# SCH_touchsensor_pressure_2024-07-11.net
KiCad netlist of a schematic drawn in EasyEDA
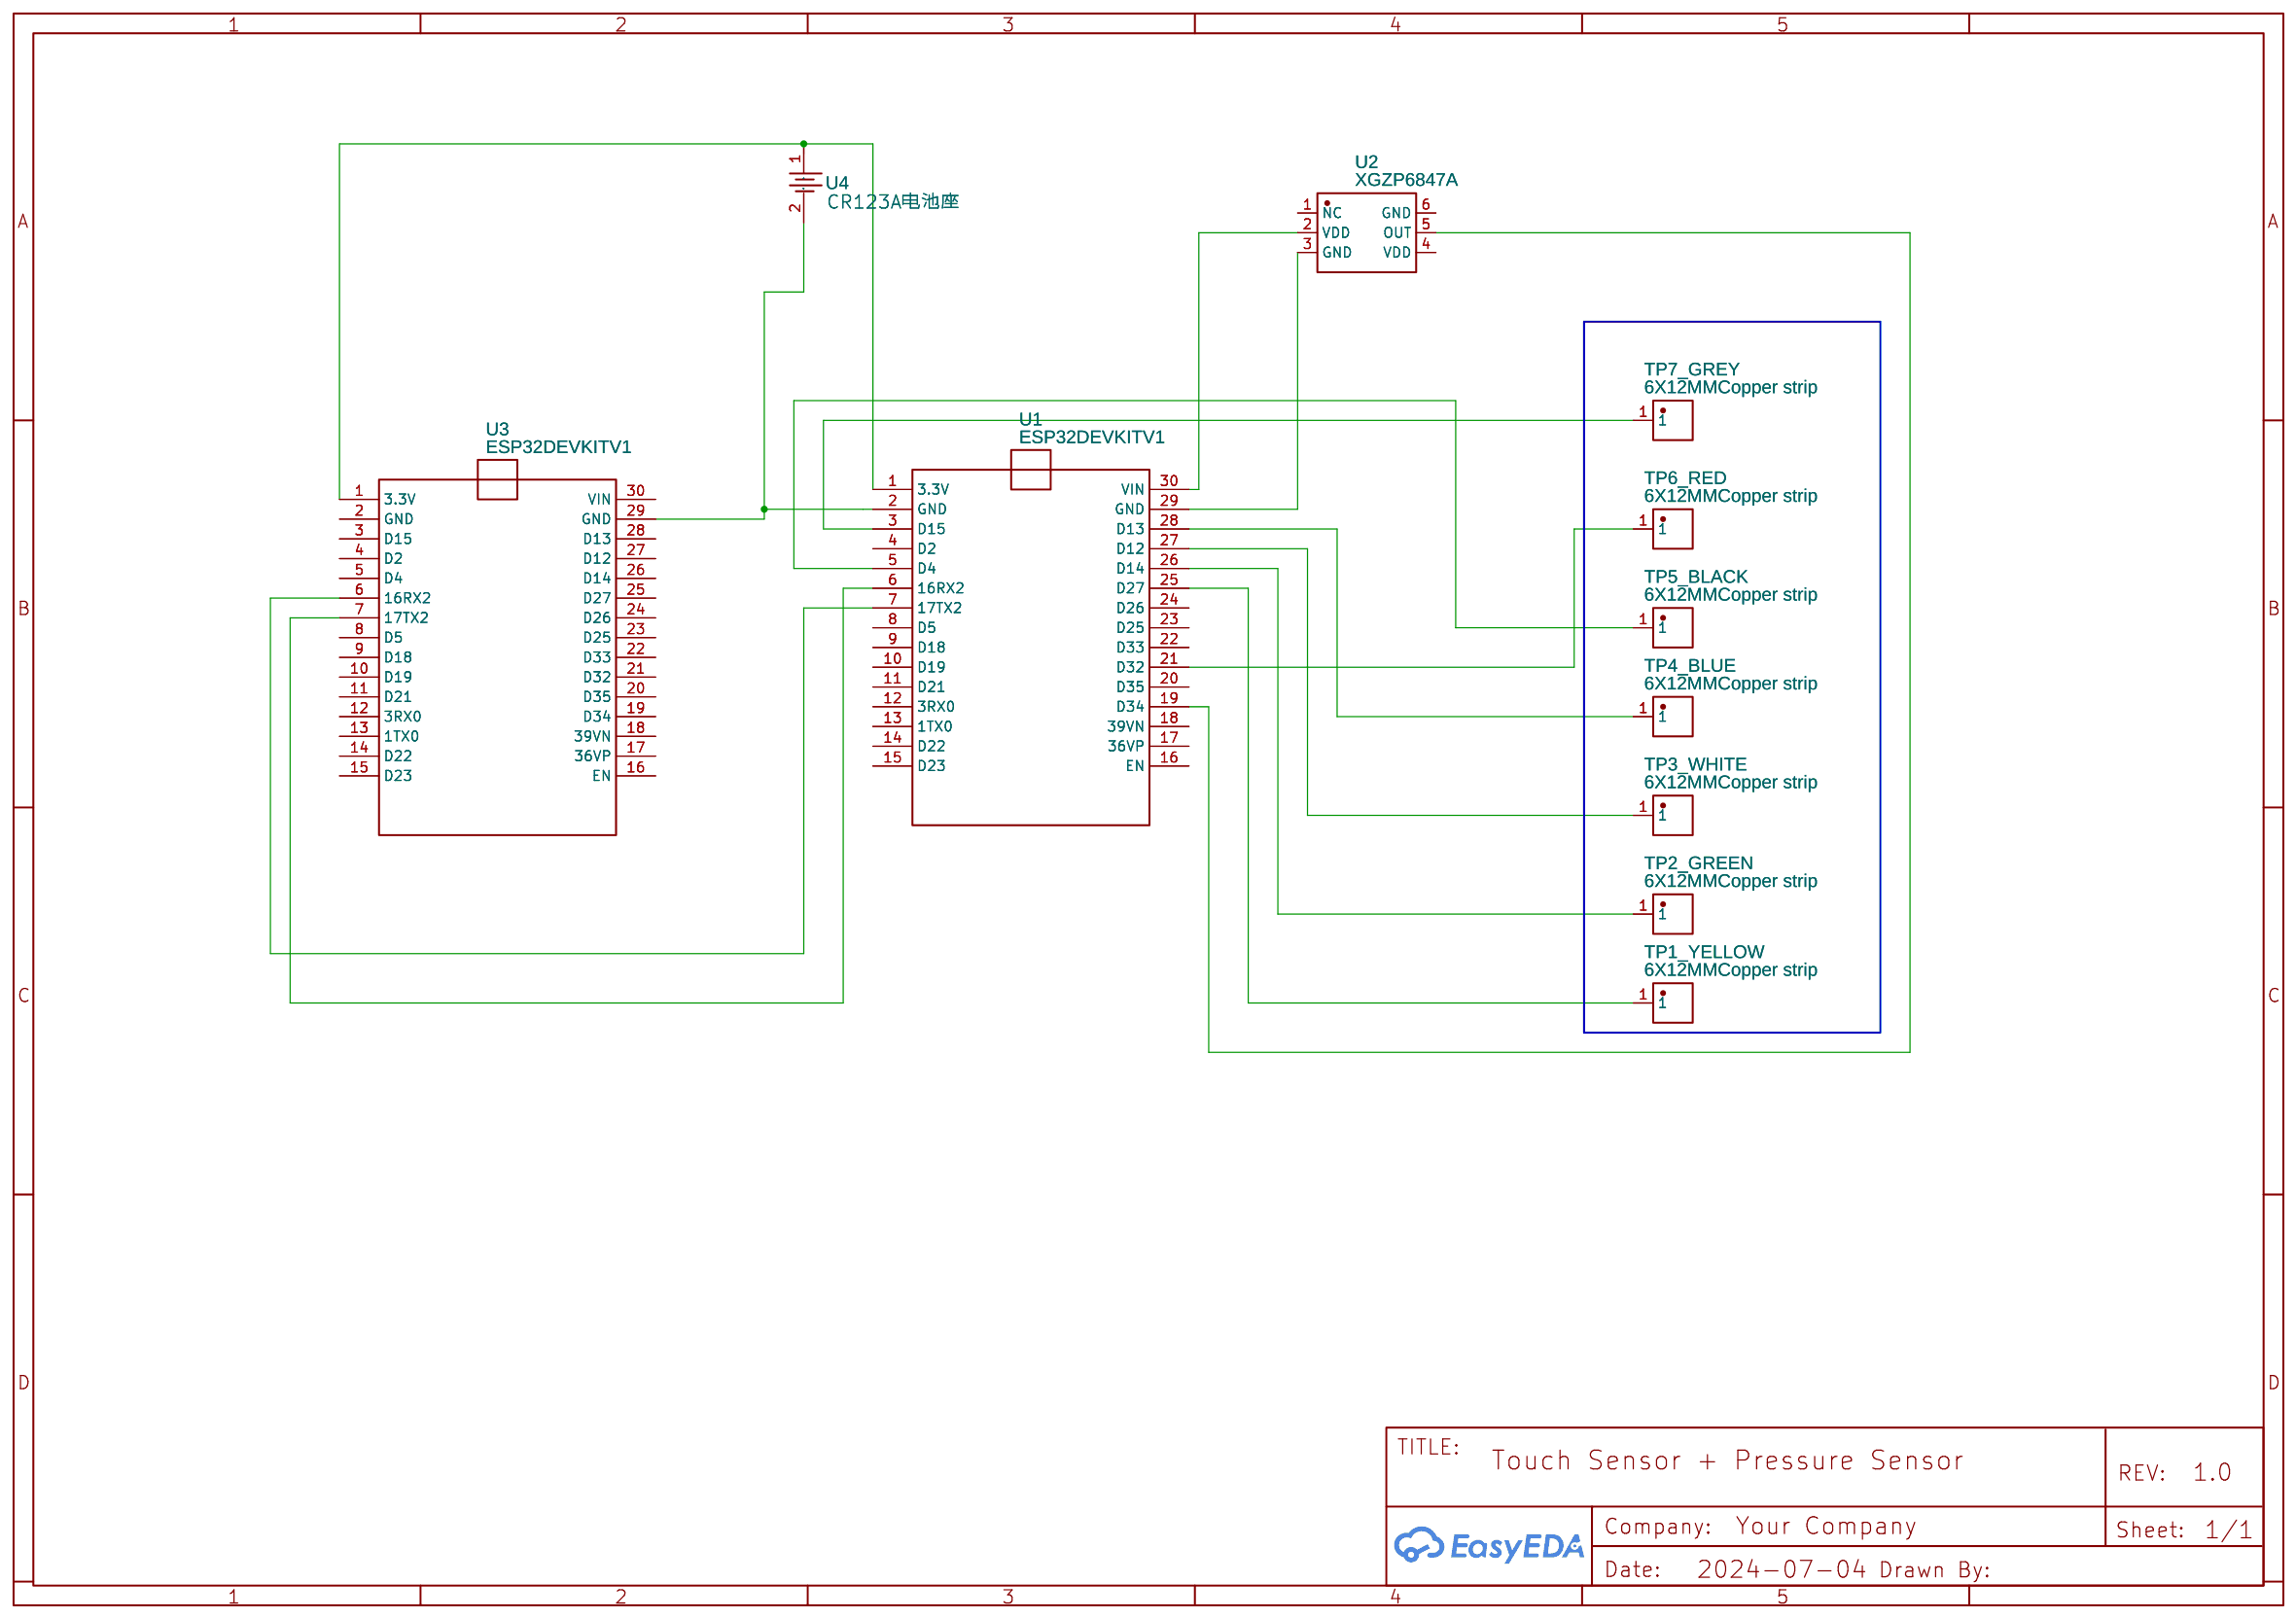
[diagram p0: schematic sheet]

(export (version "E")
  (design (tool "Eeschema 10.0.6"))
  (components
    (comp (ref "TP1_YELLOW")
      (value "6X12MMCopper strip")
      (fields (field (name "Manufacturer Part") "6X12mm铜片"))
      (libsource (lib "") (part "6X12MMCopper strip_3"))
    )
    (comp (ref "TP2_GREEN")
      (value "6X12MMCopper strip")
      (fields (field (name "Manufacturer Part") "6X12mm铜片"))
      (libsource (lib "") (part "6X12MMCopper strip"))
    )
    (comp (ref "TP3_WHITE")
      (value "6X12MMCopper strip")
      (fields (field (name "Manufacturer Part") "6X12mm铜片"))
      (libsource (lib "") (part "6X12MMCopper strip_2"))
    )
    (comp (ref "TP4_BLUE")
      (value "6X12MMCopper strip")
      (fields (field (name "Manufacturer Part") "6X12mm铜片"))
      (libsource (lib "") (part "6X12MMCopper strip_5"))
    )
    (comp (ref "TP5_BLACK")
      (value "6X12MMCopper strip")
      (fields (field (name "Manufacturer Part") "6X12mm铜片"))
      (libsource (lib "") (part "6X12MMCopper strip_1"))
    )
    (comp (ref "TP6_RED")
      (value "6X12MMCopper strip")
      (fields (field (name "Manufacturer Part") "6X12mm铜片"))
      (libsource (lib "") (part "6X12MMCopper strip_4"))
    )
    (comp (ref "TP7_GREY")
      (value "6X12MMCopper strip")
      (fields (field (name "Manufacturer Part") "6X12mm铜片"))
      (libsource (lib "") (part "6X12MMCopper strip_6"))
    )
    (comp (ref "U1") (value "ESP32DEVKITV1") (libsource (lib "") (part "ESP32DEVKITV1")))
    (comp (ref "U2") (value "XGZP6847A") (libsource (lib "") (part "XGZP6847A")))
    (comp (ref "U3") (value "ESP32DEVKITV1") (libsource (lib "") (part "ESP32DEVKITV1")))
    (comp (ref "U4") (value "CR123A电池座") (libsource (lib "") (part "CR123A电池座")))
  )
  (nets
    (net (code "1") (name "Net-(U1-3.3V)") (class "Default")
      (node (ref "U1") (pin "1") (pinfunction "3.3V_1") (pintype "unspecified"))
      (node (ref "U3") (pin "1") (pinfunction "3.3V_1") (pintype "unspecified"))
      (node (ref "U4") (pin "1") (pinfunction "1_1") (pintype "input"))
    )
    (net (code "2") (name "Net-(U1-16RX2)") (class "Default")
      (node (ref "U1") (pin "6") (pinfunction "16RX2_6") (pintype "unspecified"))
      (node (ref "U3") (pin "7") (pinfunction "17TX2_7") (pintype "unspecified"))
    )
    (net (code "3") (name "Net-(U1-17TX2)") (class "Default")
      (node (ref "U1") (pin "7") (pinfunction "17TX2_7") (pintype "unspecified"))
      (node (ref "U3") (pin "6") (pinfunction "16RX2_6") (pintype "unspecified"))
    )
    (net (code "4") (name "Net-(U1-D4)") (class "Default")
      (node (ref "TP5_BLACK") (pin "1") (pinfunction "1_1") (pintype "unspecified"))
      (node (ref "U1") (pin "5") (pinfunction "D4_5") (pintype "unspecified"))
    )
    (net (code "5") (name "Net-(U1-D12)") (class "Default")
      (node (ref "TP3_WHITE") (pin "1") (pinfunction "1_1") (pintype "unspecified"))
      (node (ref "U1") (pin "27") (pinfunction "D12_27") (pintype "unspecified"))
    )
    (net (code "6") (name "Net-(U1-D13)") (class "Default")
      (node (ref "TP4_BLUE") (pin "1") (pinfunction "1_1") (pintype "unspecified"))
      (node (ref "U1") (pin "28") (pinfunction "D13_28") (pintype "unspecified"))
    )
    (net (code "7") (name "Net-(U1-D14)") (class "Default")
      (node (ref "TP2_GREEN") (pin "1") (pinfunction "1_1") (pintype "unspecified"))
      (node (ref "U1") (pin "26") (pinfunction "D14_26") (pintype "unspecified"))
    )
    (net (code "8") (name "Net-(U1-D15)") (class "Default")
      (node (ref "TP7_GREY") (pin "1") (pinfunction "1_1") (pintype "unspecified"))
      (node (ref "U1") (pin "3") (pinfunction "D15_3") (pintype "unspecified"))
    )
    (net (code "9") (name "Net-(U1-D27)") (class "Default")
      (node (ref "TP1_YELLOW") (pin "1") (pinfunction "1_1") (pintype "unspecified"))
      (node (ref "U1") (pin "25") (pinfunction "D27_25") (pintype "unspecified"))
    )
    (net (code "10") (name "Net-(U1-D32)") (class "Default")
      (node (ref "TP6_RED") (pin "1") (pinfunction "1_1") (pintype "unspecified"))
      (node (ref "U1") (pin "21") (pinfunction "D32_21") (pintype "unspecified"))
    )
    (net (code "11") (name "Net-(U1-D34)") (class "Default")
      (node (ref "U1") (pin "19") (pinfunction "D34_19") (pintype "unspecified"))
      (node (ref "U2") (pin "5") (pinfunction "OUT_5") (pintype "unspecified"))
    )
    (net (code "12") (name "Net-(U1-GND-Pad2)") (class "Default")
      (node (ref "U1") (pin "2") (pinfunction "GND_2") (pintype "unspecified"))
      (node (ref "U3") (pin "29") (pinfunction "GND_29") (pintype "unspecified"))
      (node (ref "U4") (pin "2") (pinfunction "2_2") (pintype "input"))
    )
    (net (code "13") (name "Net-(U1-GND-Pad29)") (class "Default")
      (node (ref "U1") (pin "29") (pinfunction "GND_29") (pintype "unspecified"))
      (node (ref "U2") (pin "3") (pinfunction "GND_3") (pintype "unspecified"))
    )
    (net (code "14") (name "Net-(U1-VIN)") (class "Default")
      (node (ref "U1") (pin "30") (pinfunction "VIN_30") (pintype "unspecified"))
      (node (ref "U2") (pin "2") (pinfunction "VDD_2") (pintype "unspecified"))
    )
    (net (code "15") (name "unconnected-(U1-1TX0-Pad13)") (class "Default")
      (node (ref "U1") (pin "13") (pinfunction "1TX0_13") (pintype "unspecified"))
    )
    (net (code "16") (name "unconnected-(U1-3RX0-Pad12)") (class "Default")
      (node (ref "U1") (pin "12") (pinfunction "3RX0_12") (pintype "unspecified"))
    )
    (net (code "17") (name "unconnected-(U1-36VP-Pad17)") (class "Default")
      (node (ref "U1") (pin "17") (pinfunction "36VP_17") (pintype "unspecified"))
    )
    (net (code "18") (name "unconnected-(U1-39VN-Pad18)") (class "Default")
      (node (ref "U1") (pin "18") (pinfunction "39VN_18") (pintype "unspecified"))
    )
    (net (code "19") (name "unconnected-(U1-D2-Pad4)") (class "Default")
      (node (ref "U1") (pin "4") (pinfunction "D2_4") (pintype "unspecified"))
    )
    (net (code "20") (name "unconnected-(U1-D5-Pad8)") (class "Default")
      (node (ref "U1") (pin "8") (pinfunction "D5_8") (pintype "unspecified"))
    )
    (net (code "21") (name "unconnected-(U1-D18-Pad9)") (class "Default")
      (node (ref "U1") (pin "9") (pinfunction "D18_9") (pintype "unspecified"))
    )
    (net (code "22") (name "unconnected-(U1-D19-Pad10)") (class "Default")
      (node (ref "U1") (pin "10") (pinfunction "D19_10") (pintype "unspecified"))
    )
    (net (code "23") (name "unconnected-(U1-D21-Pad11)") (class "Default")
      (node (ref "U1") (pin "11") (pinfunction "D21_11") (pintype "unspecified"))
    )
    (net (code "24") (name "unconnected-(U1-D22-Pad14)") (class "Default")
      (node (ref "U1") (pin "14") (pinfunction "D22_14") (pintype "unspecified"))
    )
    (net (code "25") (name "unconnected-(U1-D23-Pad15)") (class "Default")
      (node (ref "U1") (pin "15") (pinfunction "D23_15") (pintype "unspecified"))
    )
    (net (code "26") (name "unconnected-(U1-D25-Pad23)") (class "Default")
      (node (ref "U1") (pin "23") (pinfunction "D25_23") (pintype "unspecified"))
    )
    (net (code "27") (name "unconnected-(U1-D26-Pad24)") (class "Default")
      (node (ref "U1") (pin "24") (pinfunction "D26_24") (pintype "unspecified"))
    )
    (net (code "28") (name "unconnected-(U1-D33-Pad22)") (class "Default")
      (node (ref "U1") (pin "22") (pinfunction "D33_22") (pintype "unspecified"))
    )
    (net (code "29") (name "unconnected-(U1-D35-Pad20)") (class "Default")
      (node (ref "U1") (pin "20") (pinfunction "D35_20") (pintype "unspecified"))
    )
    (net (code "30") (name "unconnected-(U1-EN-Pad16)") (class "Default")
      (node (ref "U1") (pin "16") (pinfunction "EN_16") (pintype "unspecified"))
    )
    (net (code "31") (name "unconnected-(U2-GND-Pad6)") (class "Default")
      (node (ref "U2") (pin "6") (pinfunction "GND_6") (pintype "unspecified"))
    )
    (net (code "32") (name "unconnected-(U2-NC-Pad1)") (class "Default")
      (node (ref "U2") (pin "1") (pinfunction "NC_1") (pintype "unspecified"))
    )
    (net (code "33") (name "unconnected-(U2-VDD-Pad4)") (class "Default")
      (node (ref "U2") (pin "4") (pinfunction "VDD_4") (pintype "unspecified"))
    )
    (net (code "34") (name "unconnected-(U3-1TX0-Pad13)") (class "Default")
      (node (ref "U3") (pin "13") (pinfunction "1TX0_13") (pintype "unspecified"))
    )
    (net (code "35") (name "unconnected-(U3-3RX0-Pad12)") (class "Default")
      (node (ref "U3") (pin "12") (pinfunction "3RX0_12") (pintype "unspecified"))
    )
    (net (code "36") (name "unconnected-(U3-36VP-Pad17)") (class "Default")
      (node (ref "U3") (pin "17") (pinfunction "36VP_17") (pintype "unspecified"))
    )
    (net (code "37") (name "unconnected-(U3-39VN-Pad18)") (class "Default")
      (node (ref "U3") (pin "18") (pinfunction "39VN_18") (pintype "unspecified"))
    )
    (net (code "38") (name "unconnected-(U3-D2-Pad4)") (class "Default")
      (node (ref "U3") (pin "4") (pinfunction "D2_4") (pintype "unspecified"))
    )
    (net (code "39") (name "unconnected-(U3-D4-Pad5)") (class "Default")
      (node (ref "U3") (pin "5") (pinfunction "D4_5") (pintype "unspecified"))
    )
    (net (code "40") (name "unconnected-(U3-D5-Pad8)") (class "Default")
      (node (ref "U3") (pin "8") (pinfunction "D5_8") (pintype "unspecified"))
    )
    (net (code "41") (name "unconnected-(U3-D12-Pad27)") (class "Default")
      (node (ref "U3") (pin "27") (pinfunction "D12_27") (pintype "unspecified"))
    )
    (net (code "42") (name "unconnected-(U3-D13-Pad28)") (class "Default")
      (node (ref "U3") (pin "28") (pinfunction "D13_28") (pintype "unspecified"))
    )
    (net (code "43") (name "unconnected-(U3-D14-Pad26)") (class "Default")
      (node (ref "U3") (pin "26") (pinfunction "D14_26") (pintype "unspecified"))
    )
    (net (code "44") (name "unconnected-(U3-D15-Pad3)") (class "Default")
      (node (ref "U3") (pin "3") (pinfunction "D15_3") (pintype "unspecified"))
    )
    (net (code "45") (name "unconnected-(U3-D18-Pad9)") (class "Default")
      (node (ref "U3") (pin "9") (pinfunction "D18_9") (pintype "unspecified"))
    )
    (net (code "46") (name "unconnected-(U3-D19-Pad10)") (class "Default")
      (node (ref "U3") (pin "10") (pinfunction "D19_10") (pintype "unspecified"))
    )
    (net (code "47") (name "unconnected-(U3-D21-Pad11)") (class "Default")
      (node (ref "U3") (pin "11") (pinfunction "D21_11") (pintype "unspecified"))
    )
    (net (code "48") (name "unconnected-(U3-D22-Pad14)") (class "Default")
      (node (ref "U3") (pin "14") (pinfunction "D22_14") (pintype "unspecified"))
    )
    (net (code "49") (name "unconnected-(U3-D23-Pad15)") (class "Default")
      (node (ref "U3") (pin "15") (pinfunction "D23_15") (pintype "unspecified"))
    )
    (net (code "50") (name "unconnected-(U3-D25-Pad23)") (class "Default")
      (node (ref "U3") (pin "23") (pinfunction "D25_23") (pintype "unspecified"))
    )
    (net (code "51") (name "unconnected-(U3-D26-Pad24)") (class "Default")
      (node (ref "U3") (pin "24") (pinfunction "D26_24") (pintype "unspecified"))
    )
    (net (code "52") (name "unconnected-(U3-D27-Pad25)") (class "Default")
      (node (ref "U3") (pin "25") (pinfunction "D27_25") (pintype "unspecified"))
    )
    (net (code "53") (name "unconnected-(U3-D32-Pad21)") (class "Default")
      (node (ref "U3") (pin "21") (pinfunction "D32_21") (pintype "unspecified"))
    )
    (net (code "54") (name "unconnected-(U3-D33-Pad22)") (class "Default")
      (node (ref "U3") (pin "22") (pinfunction "D33_22") (pintype "unspecified"))
    )
    (net (code "55") (name "unconnected-(U3-D34-Pad19)") (class "Default")
      (node (ref "U3") (pin "19") (pinfunction "D34_19") (pintype "unspecified"))
    )
    (net (code "56") (name "unconnected-(U3-D35-Pad20)") (class "Default")
      (node (ref "U3") (pin "20") (pinfunction "D35_20") (pintype "unspecified"))
    )
    (net (code "57") (name "unconnected-(U3-EN-Pad16)") (class "Default")
      (node (ref "U3") (pin "16") (pinfunction "EN_16") (pintype "unspecified"))
    )
    (net (code "58") (name "unconnected-(U3-GND-Pad2)") (class "Default")
      (node (ref "U3") (pin "2") (pinfunction "GND_2") (pintype "unspecified"))
    )
    (net (code "59") (name "unconnected-(U3-VIN-Pad30)") (class "Default")
      (node (ref "U3") (pin "30") (pinfunction "VIN_30") (pintype "unspecified"))
    )
  )
)
